# POWER.net
KiCad netlist of a schematic drawn in Altium Designer
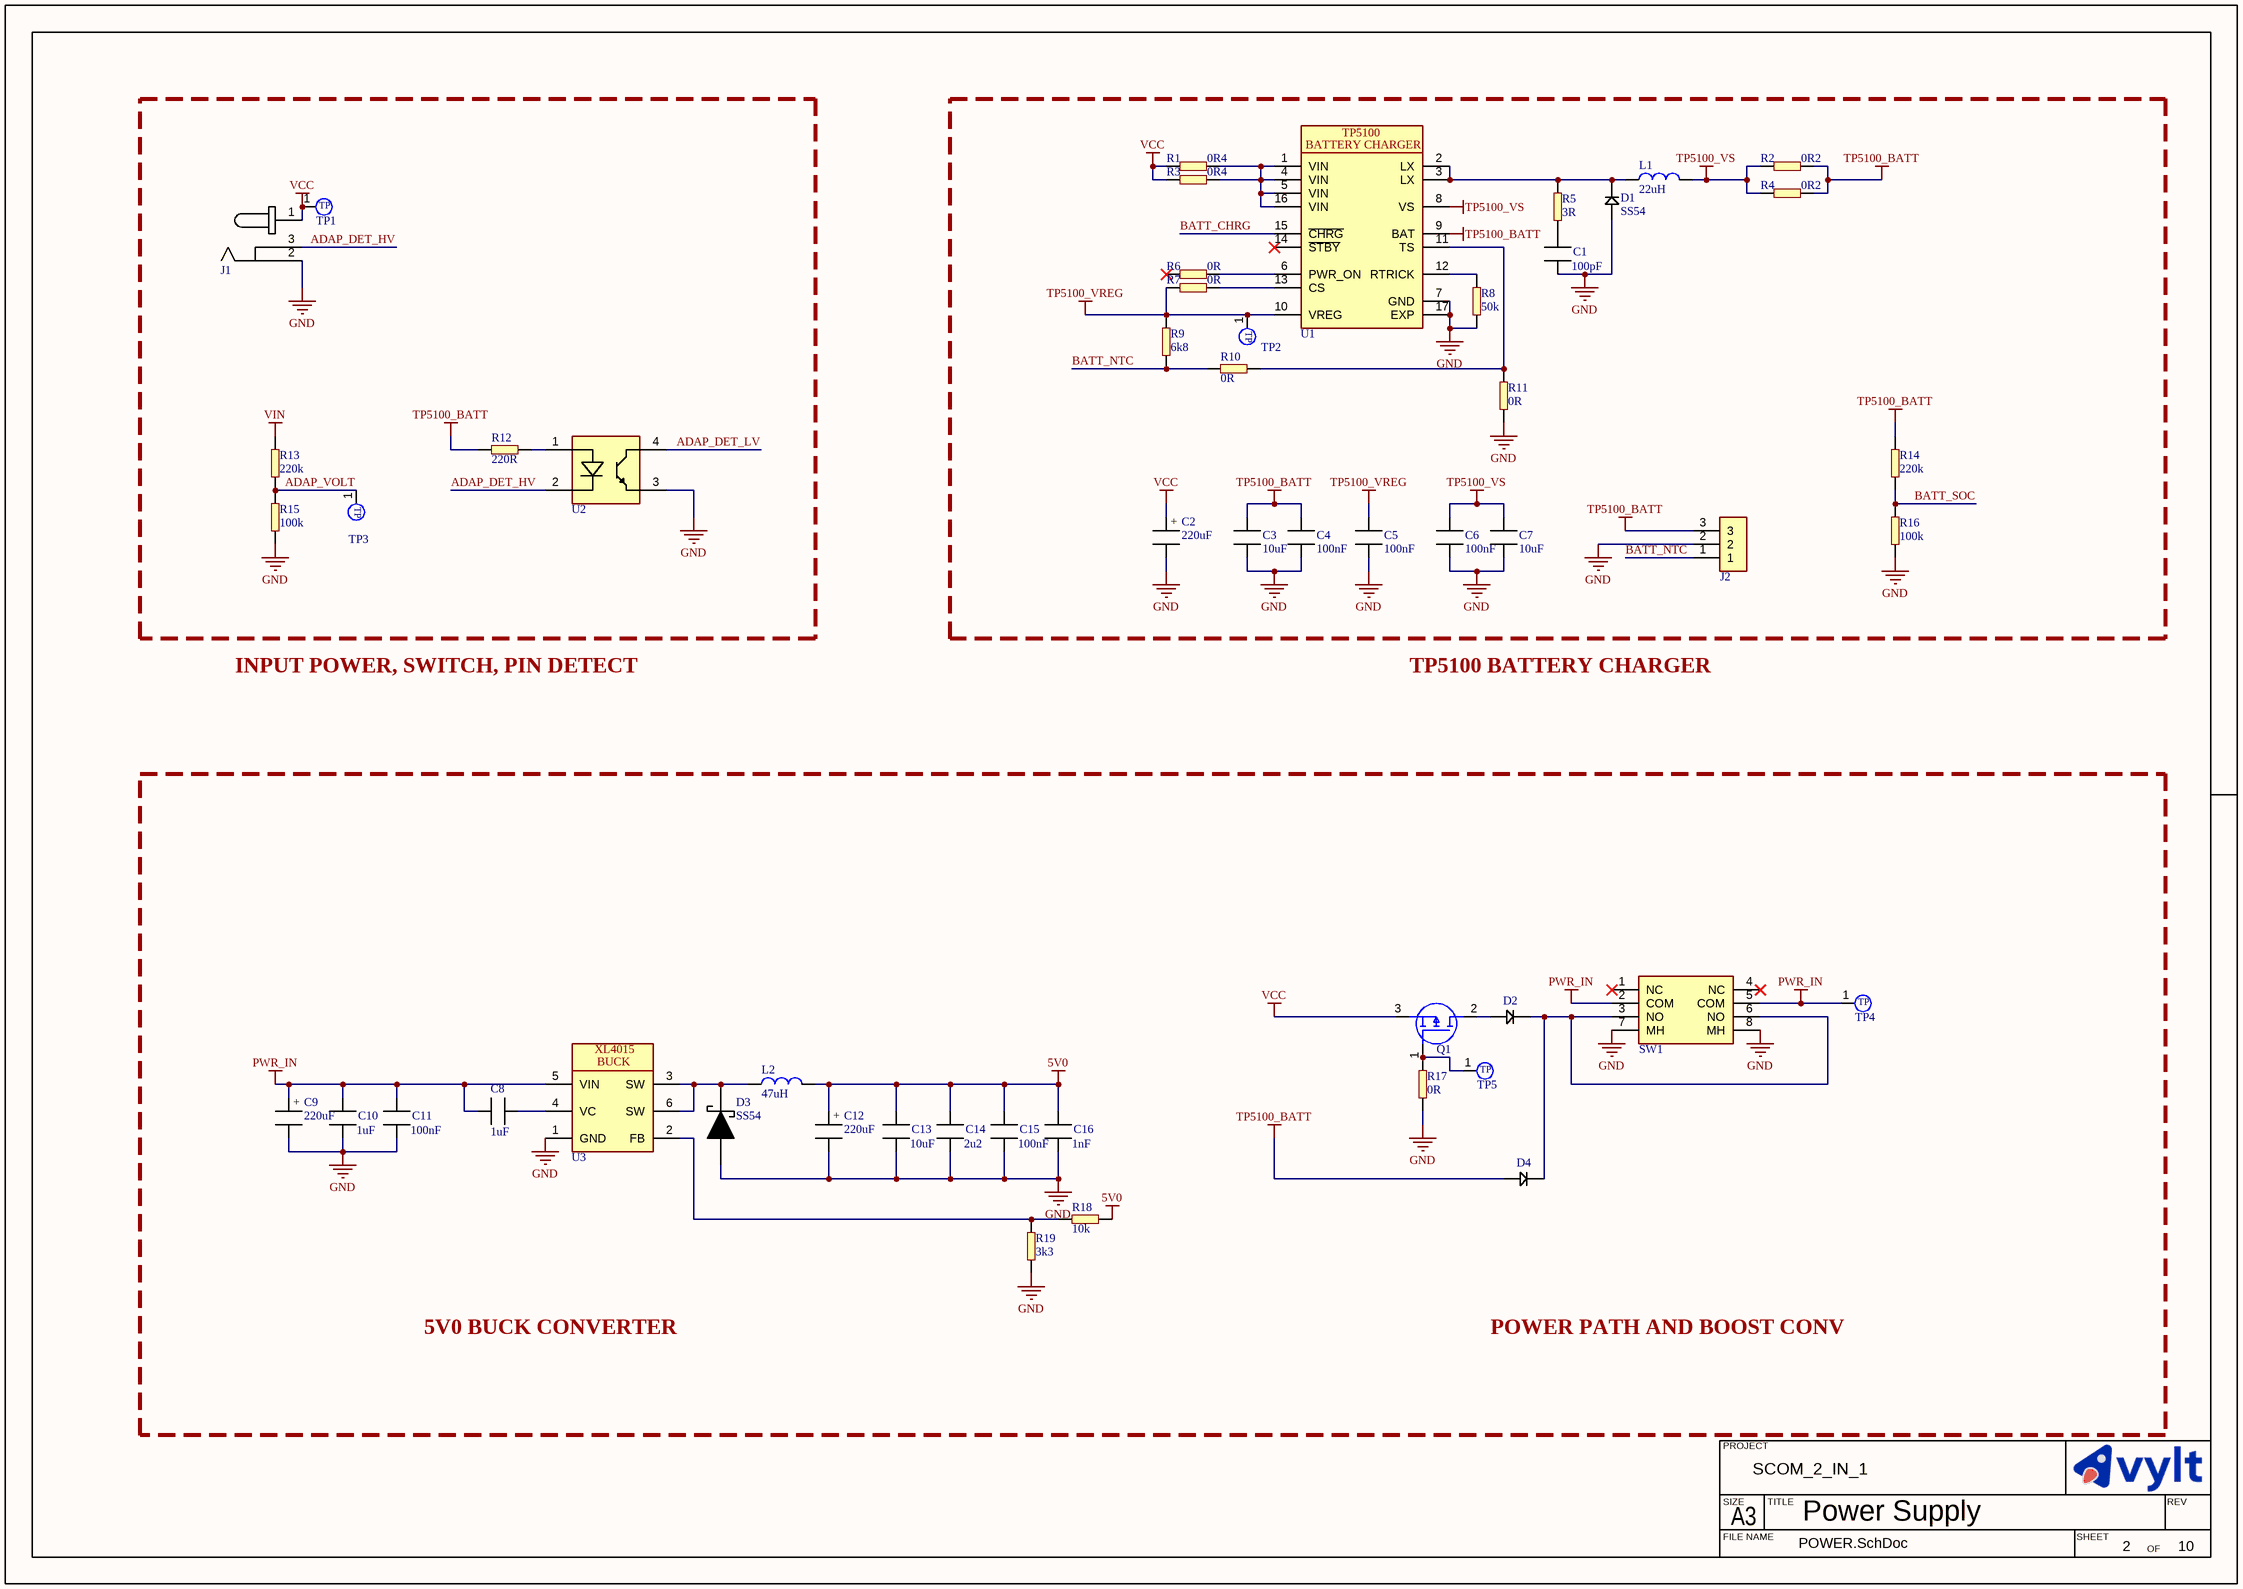
[diagram p0: POWER.SchDoc]

(export (version "E")
  (design (tool "Eeschema 10.0.6"))
  (components
    (comp (ref "C1")
      (value "100pF")
      (footprint "CAPC2012X13L")
      (description "Chip Capacitor, 2-Leads, Body 2.00x1.25mm, IPC High Density")
      (fields (field (name "Comment") "MLCC_0805"))
      (libsource (lib "Capacitor") (part "MLCC_0805"))
    )
    (comp (ref "C2")
      (value "220uF")
      (footprint "CAP_D10_H16_P5")
      (description "Electrolytic Capacitor Through Hole D10 P5.0")
      (fields (field (name "Comment") "ERP_102-2"))
      (libsource (lib "ElectrolyticCapacitor") (part "CAP_D10_H16_P5"))
    )
    (comp (ref "C3")
      (value "10uF")
      (footprint "CAPC1608X10N")
      (description "Chip Capacitor, 2-Leads, Body 1.60x0.80mm, IPC Medium Density")
      (fields (field (name "Comment") "MLCC_0603"))
      (libsource (lib "Capacitor") (part "MLCC_0603"))
    )
    (comp (ref "C4")
      (value "100nF")
      (footprint "CAPC1608X10N")
      (description "Chip Capacitor, 2-Leads, Body 1.60x0.80mm, IPC Medium Density")
      (fields (field (name "Comment") "MLCC_0603"))
      (libsource (lib "Capacitor") (part "MLCC_0603"))
    )
    (comp (ref "C5")
      (value "100nF")
      (footprint "CAPC1608X10N")
      (description "Chip Capacitor, 2-Leads, Body 1.60x0.80mm, IPC Medium Density")
      (fields (field (name "Comment") "MLCC_0603"))
      (libsource (lib "Capacitor") (part "MLCC_0603"))
    )
    (comp (ref "C6")
      (value "100nF")
      (footprint "CAPC1608X10N")
      (description "Chip Capacitor, 2-Leads, Body 1.60x0.80mm, IPC Medium Density")
      (fields (field (name "Comment") "MLCC_0603"))
      (libsource (lib "Capacitor") (part "MLCC_0603"))
    )
    (comp (ref "C7")
      (value "10uF")
      (footprint "CAPC1608X10N")
      (description "Chip Capacitor, 2-Leads, Body 1.60x0.80mm, IPC Medium Density")
      (fields (field (name "Comment") "MLCC_0603"))
      (libsource (lib "Capacitor") (part "MLCC_0603"))
    )
    (comp (ref "C8")
      (value "1uF")
      (footprint "CAPC2012X13L")
      (description "1uF 105 0805 (2012 metric) 50V X7R MLCC SMD")
      (fields (field (name "Comment") "MLCC_0805"))
      (libsource (lib "Capacitor") (part "MLCC_0805"))
    )
    (comp (ref "C9")
      (value "220uF")
      (footprint "CAP_D10_H16_P5")
      (description "Electrolytic Capacitor Through Hole D10 P5.0")
      (fields (field (name "Comment") "ERP_102-2"))
      (libsource (lib "ElectrolyticCapacitor") (part "CAP_D10_H16_P5"))
    )
    (comp (ref "C10")
      (value "1uF")
      (footprint "CAPC2012X13L")
      (description "1uF 105 0805 (2012 metric) 50V X7R MLCC SMD")
      (fields (field (name "Comment") "MLCC_0805"))
      (libsource (lib "Capacitor") (part "MLCC_0805"))
    )
    (comp (ref "C11")
      (value "100nF")
      (footprint "CAPC2012X13L")
      (description "Chip Capacitor, 2-Leads, Body 2.00x1.25mm, IPC High Density")
      (fields (field (name "Comment") "MLCC_0805"))
      (libsource (lib "Capacitor") (part "MLCC_0805"))
    )
    (comp (ref "C12")
      (value "220uF")
      (footprint "CAP_D10_H16_P5")
      (description "Electrolytic Capacitor Through Hole D10 P5.0")
      (fields (field (name "Comment") "ERP_102-2"))
      (libsource (lib "ElectrolyticCapacitor") (part "CAP_D10_H16_P5"))
    )
    (comp (ref "C13")
      (value "10uF")
      (footprint "CAPC2012X13L")
      (description "1uF 105 0805 (2012 metric) 50V X7R MLCC SMD")
      (fields (field (name "Comment") "MLCC_0805"))
      (libsource (lib "Capacitor") (part "MLCC_0805"))
    )
    (comp (ref "C14")
      (value "2u2")
      (footprint "CAPC2012X13L")
      (description "Chip Capacitor, 2-Leads, Body 2.00x1.25mm, IPC High Density")
      (fields (field (name "Comment") "MLCC_0805"))
      (libsource (lib "Capacitor") (part "MLCC_0805"))
    )
    (comp (ref "C15")
      (value "100nF")
      (footprint "CAPC2012X13L")
      (description "Chip Capacitor, 2-Leads, Body 2.00x1.25mm, IPC High Density")
      (fields (field (name "Comment") "MLCC_0805"))
      (libsource (lib "Capacitor") (part "MLCC_0805"))
    )
    (comp (ref "C16")
      (value "1nF")
      (footprint "CAPC2012X13L")
      (description "Chip Capacitor, 2-Leads, Body 2.00x1.25mm, IPC High Density")
      (fields (field (name "Comment") "MLCC_0805"))
      (libsource (lib "Capacitor") (part "MLCC_0805"))
    )
    (comp (ref "D1")
      (value "SS54")
      (footprint "DIOM6959X26L")
      (fields (field (name "Comment") "ERP_104-3"))
      (libsource (lib "Schottky") (part "SS54"))
    )
    (comp (ref "D2")
      (value "ERP_104-3")
      (footprint "DIOM6959X26L")
      (libsource (lib "Schottky") (part "SS54"))
    )
    (comp (ref "D3")
      (value "SS54")
      (footprint "DIOM6959X26L")
      (fields (field (name "Comment") "ERP_104-3"))
      (libsource (lib "") (part "SS54_1"))
    )
    (comp (ref "D4")
      (value "ERP_104-3")
      (footprint "DIOM6959X26L")
      (libsource (lib "Schottky") (part "SS54"))
    )
    (comp (ref "J1")
      (value "KLDX-0202-AC")
      (footprint "KLDX-0202-AC")
      (description "CONN PWR JACK 2X5.5MM KINKED PIN")
      (libsource (lib "Connectors") (part "KLDX-0202-AC"))
    )
    (comp (ref "J2")
      (value "Molex_5.08_3P")
      (footprint "Molex_5.08_3P")
      (description "Molex 7A 5.08mm Connector 3 Pin")
      (libsource (lib "Connectors") (part "Molex_5.08_3P"))
    )
    (comp (ref "L1")
      (value "22uH")
      (footprint "IND_1212")
      (description "IND_1212")
      (libsource (lib "Inductor") (part "IND_1212"))
    )
    (comp (ref "L2")
      (value "47uH")
      (footprint "IND_1212")
      (description "IND_1212")
      (fields (field (name "Comment") "ERP_103-3"))
      (libsource (lib "") (part "IND_1212_1"))
    )
    (comp (ref "Q1")
      (value "IRFR5305TRPBF")
      (footprint "DPAK229P991X239-3M")
      (description "P Channel MOSFET -55V HEXFET 65mOhms 42nC TO-252-3")
      (libsource (lib "MOSFET") (part "IRFR5305TRPBF"))
    )
    (comp (ref "R1")
      (value "0R4")
      (footprint "RESC3116X06M")
      (description "RES_1206")
      (libsource (lib "Resistor") (part "RES_1206"))
    )
    (comp (ref "R2")
      (value "0R2")
      (footprint "RESC3116X06M")
      (description "RES_1206")
      (libsource (lib "Resistor") (part "RES_1206"))
    )
    (comp (ref "R3")
      (value "0R4")
      (footprint "RESC3116X06M")
      (description "RES_1206")
      (libsource (lib "Resistor") (part "RES_1206"))
    )
    (comp (ref "R4")
      (value "0R2")
      (footprint "RESC3116X06M")
      (description "RES_1206")
      (libsource (lib "Resistor") (part "RES_1206"))
    )
    (comp (ref "R5")
      (value "3R")
      (footprint "RES_0603")
      (description "RES_0603")
      (fields (field (name "Comment") "ERP_101-1"))
      (libsource (lib "") (part "RES_0603_1"))
    )
    (comp (ref "R6")
      (value "0R")
      (footprint "RES_0603")
      (description "RES_0603")
      (fields (field (name "Comment") "ERP_101-1"))
      (libsource (lib "") (part "RES_0603_2"))
    )
    (comp (ref "R7")
      (value "0R")
      (footprint "RES_0603")
      (description "RES_0603")
      (fields (field (name "Comment") "ERP_101-1"))
      (libsource (lib "") (part "RES_0603_2"))
    )
    (comp (ref "R8")
      (value "50k")
      (footprint "RES_0603")
      (description "RES_0603")
      (fields (field (name "Comment") "ERP_101-1"))
      (libsource (lib "") (part "RES_0603_1"))
    )
    (comp (ref "R9")
      (value "6k8")
      (footprint "RES_0603")
      (description "RES_0603")
      (fields (field (name "Comment") "ERP_101-1"))
      (libsource (lib "") (part "RES_0603_1"))
    )
    (comp (ref "R10")
      (value "0R")
      (footprint "RES_0603")
      (description "RES_0603")
      (fields (field (name "Comment") "ERP_101-1"))
      (libsource (lib "") (part "RES_0603_3"))
    )
    (comp (ref "R11")
      (value "0R")
      (footprint "RES_0603")
      (description "RES_0603")
      (fields (field (name "Comment") "ERP_101-1"))
      (libsource (lib "") (part "RES_0603_1"))
    )
    (comp (ref "R12")
      (value "220R")
      (footprint "RES_0603")
      (description "RES_0603")
      (fields (field (name "Comment") "ERP_101-1"))
      (libsource (lib "") (part "RES_0603_2"))
    )
    (comp (ref "R13")
      (value "220k")
      (footprint "RES_0603")
      (description "RES_0603")
      (fields (field (name "Comment") "ERP_101-1"))
      (libsource (lib "") (part "RES_0603_1"))
    )
    (comp (ref "R14")
      (value "220k")
      (footprint "RES_0603")
      (description "RES_0603")
      (fields (field (name "Comment") "ERP_101-1"))
      (libsource (lib "") (part "RES_0603_1"))
    )
    (comp (ref "R15")
      (value "100k")
      (footprint "RES_0603")
      (description "RES_0603")
      (fields (field (name "Comment") "ERP_101-1"))
      (libsource (lib "Resistor") (part "RES_0603"))
    )
    (comp (ref "R16")
      (value "100k")
      (footprint "RES_0603")
      (description "RES_0603")
      (fields (field (name "Comment") "ERP_101-1"))
      (libsource (lib "") (part "RES_0603_1"))
    )
    (comp (ref "R17")
      (value "0R")
      (footprint "RES_0603")
      (description "RES_0603")
      (fields (field (name "Comment") "ERP_101-1"))
      (libsource (lib "") (part "RES_0603_1"))
    )
    (comp (ref "R18")
      (value "10k")
      (footprint "RES_0603")
      (description "RES_0603")
      (fields (field (name "Comment") "ERP_101-1"))
      (libsource (lib "") (part "RES_0603_3"))
    )
    (comp (ref "R19")
      (value "3k3")
      (footprint "RES_0603")
      (description "RES_0603")
      (fields (field (name "Comment") "ERP_101-1"))
      (libsource (lib "Resistor") (part "RES_0603"))
    )
    (comp (ref "SW1")
      (value "ERP_110-4")
      (footprint "PBH2U")
      (description "Pushbutton Switch DPDT Standard Through Hole, Right Angle")
      (libsource (lib "Switch") (part "PBH2U"))
    )
    (comp (ref "TP1") (value "TP_1MM") (footprint "TP_1MM") (libsource (lib "Jumper") (part "TP_1MM")))
    (comp (ref "TP2") (value "TP_1MM") (footprint "TP_1MM") (libsource (lib "Jumper") (part "TP_1MM")))
    (comp (ref "TP3") (value "TP_1MM") (footprint "TP_1MM") (libsource (lib "Jumper") (part "TP_1MM")))
    (comp (ref "TP4") (value "TP_1MM") (footprint "TP_1MM") (libsource (lib "Jumper") (part "TP_1MM")))
    (comp (ref "TP5") (value "TP_1MM") (footprint "TP_1MM") (libsource (lib "Jumper") (part "TP_1MM")))
    (comp (ref "U1")
      (value "TP5100")
      (footprint "QFN65P400X400X90_HS-17M")
      (description "Switching-buck type (double 8.4V / single 4.2V) lithium battery charging management chip")
      (libsource (lib "BatteryCharger") (part "TP5100"))
    )
    (comp (ref "U2")
      (value "FOD817A3SD")
      (footprint "FOD817A3SD")
      (description "OPTOISOLATOR 5KV TRANSISTOR 4SMD")
      (libsource (lib "Optocoupler") (part "FOD817A3SD"))
    )
    (comp (ref "U3")
      (value "XL4015")
      (footprint "XL4015")
      (description "5A 180KHz 36V Buck DC to DC Converter")
      (libsource (lib "DCDC_Switcher") (part "XL4015"))
    )
  )
  (nets
    (net (code "1") (name "/ADAP_DET_HV") (class "Default")
      (node (ref "J1") (pin "3") (pinfunction "3_3") (pintype "passive"))
      (node (ref "U2") (pin "2") (pinfunction "CATHODE_2") (pintype "passive"))
    )
    (net (code "2") (name "/ADAP_DET_LV") (class "Default")
      (node (ref "U2") (pin "4") (pinfunction "COLLECTOR_4") (pintype "passive"))
    )
    (net (code "3") (name "/ADAP_VOLT") (class "Default")
      (node (ref "R13") (pin "1") (pinfunction "1_1") (pintype "passive"))
      (node (ref "R15") (pin "1") (pinfunction "1_1") (pintype "passive"))
      (node (ref "TP3") (pin "1") (pinfunction "1_1") (pintype "passive"))
    )
    (net (code "4") (name "/BATT_CHRG") (class "Default")
      (node (ref "U1") (pin "15") (pinfunction "~{CHRG}_15") (pintype "passive"))
    )
    (net (code "5") (name "/BATT_NTC") (class "Default")
      (node (ref "J2") (pin "1") (pinfunction "1_1") (pintype "passive"))
      (node (ref "R10") (pin "2") (pinfunction "2_2") (pintype "passive"))
      (node (ref "R9") (pin "1") (pinfunction "1_1") (pintype "passive"))
    )
    (net (code "6") (name "/BATT_SOC") (class "Default")
      (node (ref "R14") (pin "1") (pinfunction "1_1") (pintype "passive"))
      (node (ref "R16") (pin "2") (pinfunction "2_2") (pintype "passive"))
    )
    (net (code "7") (name "5V0") (class "Default")
      (node (ref "C12") (pin "1") (pinfunction "1_1") (pintype "passive"))
      (node (ref "C13") (pin "1") (pinfunction "1_1") (pintype "passive"))
      (node (ref "C14") (pin "1") (pinfunction "1_1") (pintype "passive"))
      (node (ref "C15") (pin "1") (pinfunction "1_1") (pintype "passive"))
      (node (ref "C16") (pin "1") (pinfunction "1_1") (pintype "passive"))
      (node (ref "L2") (pin "1") (pinfunction "1_1") (pintype "passive"))
      (node (ref "R18") (pin "1") (pinfunction "1_1") (pintype "passive"))
    )
    (net (code "8") (name "GND") (class "Default")
      (node (ref "C1") (pin "2") (pinfunction "2_2") (pintype "passive"))
      (node (ref "C10") (pin "2") (pinfunction "2_2") (pintype "passive"))
      (node (ref "C11") (pin "2") (pinfunction "2_2") (pintype "passive"))
      (node (ref "C12") (pin "2") (pinfunction "2_2") (pintype "passive"))
      (node (ref "C13") (pin "2") (pinfunction "2_2") (pintype "passive"))
      (node (ref "C14") (pin "2") (pinfunction "2_2") (pintype "passive"))
      (node (ref "C15") (pin "2") (pinfunction "2_2") (pintype "passive"))
      (node (ref "C16") (pin "2") (pinfunction "2_2") (pintype "passive"))
      (node (ref "C2") (pin "2") (pinfunction "2_2") (pintype "passive"))
      (node (ref "C3") (pin "2") (pinfunction "2_2") (pintype "passive"))
      (node (ref "C4") (pin "2") (pinfunction "2_2") (pintype "passive"))
      (node (ref "C5") (pin "2") (pinfunction "2_2") (pintype "passive"))
      (node (ref "C6") (pin "2") (pinfunction "2_2") (pintype "passive"))
      (node (ref "C7") (pin "2") (pinfunction "2_2") (pintype "passive"))
      (node (ref "C9") (pin "2") (pinfunction "2_2") (pintype "passive"))
      (node (ref "D1") (pin "2") (pinfunction "A_2") (pintype "passive"))
      (node (ref "D3") (pin "2") (pinfunction "A_2") (pintype "passive"))
      (node (ref "J1") (pin "2") (pinfunction "2_2") (pintype "passive"))
      (node (ref "J2") (pin "2") (pinfunction "2_2") (pintype "passive"))
      (node (ref "R11") (pin "1") (pinfunction "1_1") (pintype "passive"))
      (node (ref "R15") (pin "2") (pinfunction "2_2") (pintype "passive"))
      (node (ref "R16") (pin "1") (pinfunction "1_1") (pintype "passive"))
      (node (ref "R17") (pin "1") (pinfunction "1_1") (pintype "passive"))
      (node (ref "R19") (pin "2") (pinfunction "2_2") (pintype "passive"))
      (node (ref "R8") (pin "1") (pinfunction "1_1") (pintype "passive"))
      (node (ref "SW1") (pin "7") (pinfunction "MH_7") (pintype "passive"))
      (node (ref "SW1") (pin "8") (pinfunction "MH_8") (pintype "passive"))
      (node (ref "U1") (pin "17") (pinfunction "EXP_17") (pintype "passive"))
      (node (ref "U1") (pin "7") (pinfunction "GND_7") (pintype "passive"))
      (node (ref "U2") (pin "3") (pinfunction "EMITTER_3") (pintype "passive"))
      (node (ref "U3") (pin "1") (pinfunction "GND_1") (pintype "passive"))
    )
    (net (code "9") (name "Net-(C1-Pad1)") (class "Default")
      (node (ref "C1") (pin "1") (pinfunction "1_1") (pintype "passive"))
      (node (ref "R5") (pin "1") (pinfunction "1_1") (pintype "passive"))
    )
    (net (code "10") (name "Net-(D1-C)") (class "Default")
      (node (ref "D1") (pin "1") (pinfunction "C_1") (pintype "passive"))
      (node (ref "L1") (pin "1") (pinfunction "1_1") (pintype "passive"))
      (node (ref "R5") (pin "2") (pinfunction "2_2") (pintype "passive"))
      (node (ref "U1") (pin "2") (pinfunction "LX_2") (pintype "passive"))
      (node (ref "U1") (pin "3") (pinfunction "LX_3") (pintype "passive"))
    )
    (net (code "11") (name "Net-(D2-A)") (class "Default")
      (node (ref "D2") (pin "2") (pinfunction "A_2") (pintype "passive"))
      (node (ref "Q1") (pin "2") (pinfunction "D_2") (pintype "passive"))
    )
    (net (code "12") (name "Net-(D2-C)") (class "Default")
      (node (ref "D2") (pin "1") (pinfunction "C_1") (pintype "passive"))
      (node (ref "D4") (pin "1") (pinfunction "C_1") (pintype "passive"))
      (node (ref "SW1") (pin "3") (pinfunction "NO_3") (pintype "passive"))
      (node (ref "SW1") (pin "6") (pinfunction "NO_6") (pintype "passive"))
    )
    (net (code "13") (name "Net-(D3-C)") (class "Default")
      (node (ref "D3") (pin "1") (pinfunction "C_1") (pintype "passive"))
      (node (ref "L2") (pin "2") (pinfunction "2_2") (pintype "passive"))
      (node (ref "U3") (pin "3") (pinfunction "SW_3") (pintype "passive"))
      (node (ref "U3") (pin "6") (pinfunction "SW_6") (pintype "passive"))
    )
    (net (code "14") (name "Net-(Q1-G)") (class "Default")
      (node (ref "Q1") (pin "1") (pinfunction "G_1") (pintype "passive"))
      (node (ref "R17") (pin "2") (pinfunction "2_2") (pintype "passive"))
      (node (ref "TP5") (pin "1") (pinfunction "1_1") (pintype "passive"))
    )
    (net (code "15") (name "Net-(R1-Pad1)") (class "Default")
      (node (ref "R1") (pin "1") (pinfunction "1_1") (pintype "passive"))
      (node (ref "R3") (pin "1") (pinfunction "1_1") (pintype "passive"))
      (node (ref "U1") (pin "1") (pinfunction "VIN_1") (pintype "passive"))
      (node (ref "U1") (pin "16") (pinfunction "VIN_16") (pintype "passive"))
      (node (ref "U1") (pin "4") (pinfunction "VIN_4") (pintype "passive"))
      (node (ref "U1") (pin "5") (pinfunction "VIN_5") (pintype "passive"))
    )
    (net (code "16") (name "Net-(U1-CS)") (class "Default")
      (node (ref "R7") (pin "2") (pinfunction "2_2") (pintype "passive"))
      (node (ref "U1") (pin "13") (pinfunction "CS_13") (pintype "passive"))
    )
    (net (code "17") (name "Net-(U1-PWR_ON)") (class "Default")
      (node (ref "R6") (pin "2") (pinfunction "2_2") (pintype "passive"))
      (node (ref "U1") (pin "6") (pinfunction "PWR_ON_6") (pintype "passive"))
    )
    (net (code "18") (name "Net-(U1-RTRICK)") (class "Default")
      (node (ref "R8") (pin "2") (pinfunction "2_2") (pintype "passive"))
      (node (ref "U1") (pin "12") (pinfunction "RTRICK_12") (pintype "passive"))
    )
    (net (code "19") (name "Net-(U1-TS)") (class "Default")
      (node (ref "R10") (pin "1") (pinfunction "1_1") (pintype "passive"))
      (node (ref "R11") (pin "2") (pinfunction "2_2") (pintype "passive"))
      (node (ref "U1") (pin "11") (pinfunction "TS_11") (pintype "passive"))
    )
    (net (code "20") (name "Net-(U2-ANODE)") (class "Default")
      (node (ref "R12") (pin "2") (pinfunction "2_2") (pintype "passive"))
      (node (ref "U2") (pin "1") (pinfunction "ANODE_1") (pintype "passive"))
    )
    (net (code "21") (name "Net-(U3-FB)") (class "Default")
      (node (ref "R18") (pin "2") (pinfunction "2_2") (pintype "passive"))
      (node (ref "R19") (pin "1") (pinfunction "1_1") (pintype "passive"))
      (node (ref "U3") (pin "2") (pinfunction "FB_2") (pintype "passive"))
    )
    (net (code "22") (name "Net-(U3-VC)") (class "Default")
      (node (ref "C8") (pin "2") (pinfunction "2_2") (pintype "passive"))
      (node (ref "U3") (pin "4") (pinfunction "VC_4") (pintype "passive"))
    )
    (net (code "23") (name "PWR_IN") (class "Default")
      (node (ref "C10") (pin "1") (pinfunction "1_1") (pintype "passive"))
      (node (ref "C11") (pin "1") (pinfunction "1_1") (pintype "passive"))
      (node (ref "C8") (pin "1") (pinfunction "1_1") (pintype "passive"))
      (node (ref "C9") (pin "1") (pinfunction "1_1") (pintype "passive"))
      (node (ref "SW1") (pin "2") (pinfunction "COM_2") (pintype "passive"))
      (node (ref "SW1") (pin "5") (pinfunction "COM_5") (pintype "passive"))
      (node (ref "TP4") (pin "1") (pinfunction "1_1") (pintype "passive"))
      (node (ref "U3") (pin "5") (pinfunction "VIN_5") (pintype "passive"))
    )
    (net (code "24") (name "TP5100_BATT") (class "Default")
      (node (ref "C3") (pin "1") (pinfunction "1_1") (pintype "passive"))
      (node (ref "C4") (pin "1") (pinfunction "1_1") (pintype "passive"))
      (node (ref "D4") (pin "2") (pinfunction "A_2") (pintype "passive"))
      (node (ref "J2") (pin "3") (pinfunction "3_3") (pintype "passive"))
      (node (ref "R12") (pin "1") (pinfunction "1_1") (pintype "passive"))
      (node (ref "R14") (pin "2") (pinfunction "2_2") (pintype "passive"))
      (node (ref "R2") (pin "1") (pinfunction "1_1") (pintype "passive"))
      (node (ref "R4") (pin "1") (pinfunction "1_1") (pintype "passive"))
      (node (ref "U1") (pin "9") (pinfunction "BAT_9") (pintype "passive"))
    )
    (net (code "25") (name "TP5100_VREG") (class "Default")
      (node (ref "C5") (pin "1") (pinfunction "1_1") (pintype "passive"))
      (node (ref "R7") (pin "1") (pinfunction "1_1") (pintype "passive"))
      (node (ref "R9") (pin "2") (pinfunction "2_2") (pintype "passive"))
      (node (ref "TP2") (pin "1") (pinfunction "1_1") (pintype "passive"))
      (node (ref "U1") (pin "10") (pinfunction "VREG_10") (pintype "passive"))
    )
    (net (code "26") (name "TP5100_VS") (class "Default")
      (node (ref "C6") (pin "1") (pinfunction "1_1") (pintype "passive"))
      (node (ref "C7") (pin "1") (pinfunction "1_1") (pintype "passive"))
      (node (ref "L1") (pin "2") (pinfunction "2_2") (pintype "passive"))
      (node (ref "R2") (pin "2") (pinfunction "2_2") (pintype "passive"))
      (node (ref "R4") (pin "2") (pinfunction "2_2") (pintype "passive"))
      (node (ref "U1") (pin "8") (pinfunction "VS_8") (pintype "passive"))
    )
    (net (code "27") (name "VCC") (class "Default")
      (node (ref "C2") (pin "1") (pinfunction "1_1") (pintype "passive"))
      (node (ref "J1") (pin "1") (pinfunction "1_1") (pintype "passive"))
      (node (ref "Q1") (pin "3") (pinfunction "S_3") (pintype "passive"))
      (node (ref "R1") (pin "2") (pinfunction "2_2") (pintype "passive"))
      (node (ref "R3") (pin "2") (pinfunction "2_2") (pintype "passive"))
      (node (ref "TP1") (pin "1") (pinfunction "1_1") (pintype "passive"))
    )
    (net (code "28") (name "VIN") (class "Default")
      (node (ref "R13") (pin "2") (pinfunction "2_2") (pintype "passive"))
    )
    (net (code "29") (name "unconnected-(R6-Pad1)") (class "Default")
      (node (ref "R6") (pin "1") (pinfunction "1_1") (pintype "passive+no_connect"))
    )
    (net (code "30") (name "unconnected-(SW1-NC-Pad1)") (class "Default")
      (node (ref "SW1") (pin "1") (pinfunction "NC_1") (pintype "passive+no_connect"))
    )
    (net (code "31") (name "unconnected-(SW1-NC-Pad4)") (class "Default")
      (node (ref "SW1") (pin "4") (pinfunction "NC_4") (pintype "passive+no_connect"))
    )
    (net (code "32") (name "unconnected-(U1-~{STBY}-Pad14)") (class "Default")
      (node (ref "U1") (pin "14") (pinfunction "~{STBY}_14") (pintype "passive+no_connect"))
    )
  )
)
